# outsidePromini.net
KiCad netlist of a schematic drawn in EAGLE
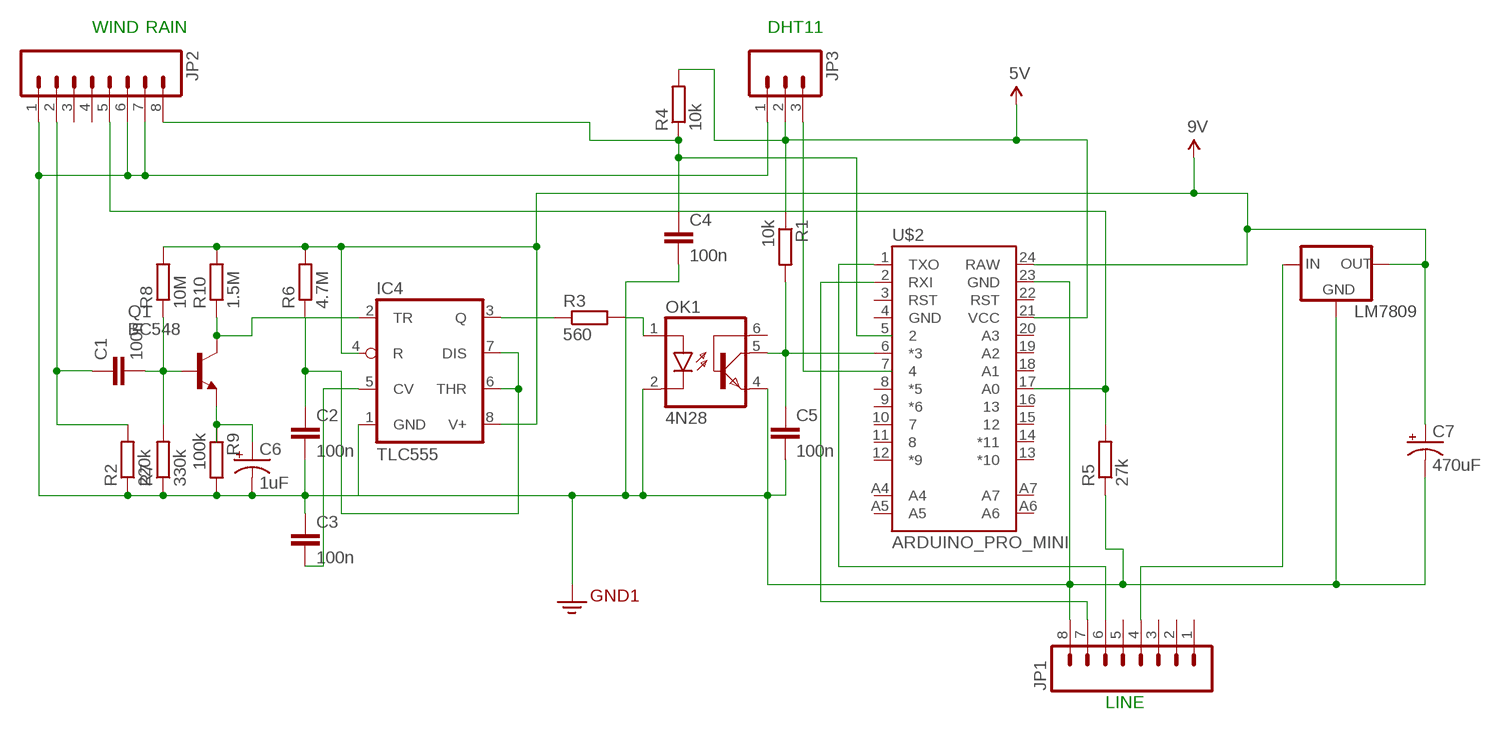
[diagram p0: schematic, sheet 1]

(export (version "E")
  (design (tool "Eeschema 10.0.6"))
  (components
    (comp (ref "C1")
      (value "100n")
      (footprint "eagle-import:CAP-PTH-SMALL-KIT")
      (libsource (lib "eagle-import") (part "0.1UF-50V-20%(PTH)KIT-EZ"))
    )
    (comp (ref "C2")
      (value "100n")
      (footprint "eagle-import:CAP-PTH-SMALL-KIT")
      (libsource (lib "eagle-import") (part "0.1UF-50V-20%(PTH)KIT-EZ"))
    )
    (comp (ref "C3")
      (value "100n")
      (footprint "eagle-import:CAP-PTH-SMALL-KIT")
      (libsource (lib "eagle-import") (part "0.1UF-50V-20%(PTH)KIT-EZ"))
    )
    (comp (ref "C4")
      (value "100n")
      (footprint "eagle-import:CAP-PTH-SMALL-KIT")
      (libsource (lib "eagle-import") (part "0.1UF-50V-20%(PTH)KIT-EZ"))
    )
    (comp (ref "C5")
      (value "100n")
      (footprint "eagle-import:CAP-PTH-SMALL-KIT")
      (libsource (lib "eagle-import") (part "0.1UF-50V-20%(PTH)KIT-EZ"))
    )
    (comp (ref "C6")
      (value "1uF")
      (footprint "eagle-import:CPOL-RADIAL-100UF-25V")
      (libsource (lib "eagle-import") (part "CAP_POLPTH1"))
    )
    (comp (ref "C7")
      (value "470uF")
      (footprint "eagle-import:CPOL-RADIAL-100UF-25V")
      (libsource (lib "eagle-import") (part "CAP_POLPTH1"))
    )
    (comp (ref "IC4")
      (value "TLC555")
      (footprint "eagle-import:DIL08")
      (libsource (lib "eagle-import") (part "555NLM"))
    )
    (comp (ref "JP1")
      (value "M08LOCK_LONGPADS")
      (footprint "eagle-import:1X08_LOCK_LONGPADS")
      (libsource (lib "eagle-import") (part "M08LOCK_LONGPADS"))
    )
    (comp (ref "JP2")
      (value "M08LOCK_LONGPADS")
      (footprint "eagle-import:1X08_LOCK_LONGPADS")
      (libsource (lib "eagle-import") (part "M08LOCK_LONGPADS"))
    )
    (comp (ref "JP3")
      (value "M03LOCK_LONGPADS")
      (footprint "eagle-import:1X03_LOCK_LONGPADS")
      (libsource (lib "eagle-import") (part "M03LOCK_LONGPADS"))
    )
    (comp (ref "LM7809")
      (value "78XXS")
      (footprint "eagle-import:78XXS")
      (libsource (lib "eagle-import") (part "78XXS"))
    )
    (comp (ref "OK1")
      (value "4N28")
      (footprint "eagle-import:DIL06")
      (fields (field (name "MF") "FAIRCHILD SEMICONDUCTOR") (field (name "MPN") "4N37"))
      (libsource (lib "eagle-import") (part "4N37"))
    )
    (comp (ref "Q1")
      (value "BC548")
      (footprint "eagle-import:TO92-EBC")
      (libsource (lib "eagle-import") (part "BC548"))
    )
    (comp (ref "R1")
      (value "10k")
      (footprint "eagle-import:0204_5")
      (libsource (lib "eagle-import") (part "R-EU_0204/5"))
    )
    (comp (ref "R2")
      (value "220k")
      (footprint "eagle-import:0204_5")
      (libsource (lib "eagle-import") (part "R-EU_0204/5"))
    )
    (comp (ref "R3")
      (value "560")
      (footprint "eagle-import:0204_5")
      (libsource (lib "eagle-import") (part "R-EU_0204/5"))
    )
    (comp (ref "R4")
      (value "10k")
      (footprint "eagle-import:0204_5")
      (libsource (lib "eagle-import") (part "R-EU_0204/5"))
    )
    (comp (ref "R5")
      (value "27k")
      (footprint "eagle-import:0204_5")
      (libsource (lib "eagle-import") (part "R-EU_0204/5"))
    )
    (comp (ref "R6")
      (value "4.7M")
      (footprint "eagle-import:0204_5")
      (libsource (lib "eagle-import") (part "R-EU_0204/5"))
    )
    (comp (ref "R7")
      (value "330k")
      (footprint "eagle-import:0204_5")
      (libsource (lib "eagle-import") (part "R-EU_0204/5"))
    )
    (comp (ref "R8")
      (value "10M")
      (footprint "eagle-import:0204_5")
      (libsource (lib "eagle-import") (part "R-EU_0204/5"))
    )
    (comp (ref "R9")
      (value "100k")
      (footprint "eagle-import:0204_5")
      (libsource (lib "eagle-import") (part "R-EU_0204/5"))
    )
    (comp (ref "R10")
      (value "1.5M")
      (footprint "eagle-import:0204_5")
      (libsource (lib "eagle-import") (part "R-EU_0204/5"))
    )
    (comp (ref "U$2")
      (value "ARDUINO_PRO_MINI")
      (footprint "eagle-import:ARDUINO_PRO_MINI")
      (libsource (lib "eagle-import") (part "ARDUINO_PRO_MINI"))
    )
  )
  (nets
    (net (code "1") (name "5V") (class "Default")
      (node (ref "C7") (pin "1") (pinfunction "+_1") (pintype "passive"))
      (node (ref "IC4") (pin "4") (pinfunction "R_4") (pintype "input"))
      (node (ref "IC4") (pin "8") (pinfunction "V+_8") (pintype "power_in"))
      (node (ref "JP3") (pin "2") (pinfunction "2_2") (pintype "passive"))
      (node (ref "LM7809") (pin "OUT") (pinfunction "OUT_OUT") (pintype "passive"))
      (node (ref "R1") (pin "1") (pinfunction "1_1") (pintype "passive"))
      (node (ref "R10") (pin "2") (pinfunction "2_2") (pintype "passive"))
      (node (ref "R4") (pin "2") (pinfunction "2_2") (pintype "passive"))
      (node (ref "R6") (pin "2") (pinfunction "2_2") (pintype "passive"))
      (node (ref "R8") (pin "2") (pinfunction "2_2") (pintype "passive"))
      (node (ref "U$2") (pin "21") (pinfunction "VCC_21") (pintype "bidirectional"))
      (node (ref "U$2") (pin "24") (pinfunction "RAW_24") (pintype "bidirectional"))
    )
    (net (code "2") (name "GND") (class "Default")
      (node (ref "C2") (pin "2") (pinfunction "2_2") (pintype "passive"))
      (node (ref "C3") (pin "1") (pinfunction "1_1") (pintype "passive"))
      (node (ref "C4") (pin "2") (pinfunction "2_2") (pintype "passive"))
      (node (ref "C5") (pin "2") (pinfunction "2_2") (pintype "passive"))
      (node (ref "C6") (pin "2") (pinfunction "-_2") (pintype "passive"))
      (node (ref "C7") (pin "2") (pinfunction "-_2") (pintype "passive"))
      (node (ref "IC4") (pin "1") (pinfunction "GND_1") (pintype "power_in"))
      (node (ref "JP1") (pin "8") (pinfunction "8_8") (pintype "passive"))
      (node (ref "JP2") (pin "1") (pinfunction "1_1") (pintype "passive"))
      (node (ref "JP2") (pin "6") (pinfunction "6_6") (pintype "passive"))
      (node (ref "JP2") (pin "7") (pinfunction "7_7") (pintype "passive"))
      (node (ref "JP3") (pin "1") (pinfunction "1_1") (pintype "passive"))
      (node (ref "LM7809") (pin "GND") (pinfunction "GND_GND") (pintype "input"))
      (node (ref "OK1") (pin "2") (pinfunction "C_2") (pintype "passive"))
      (node (ref "OK1") (pin "4") (pinfunction "EMI_4") (pintype "passive"))
      (node (ref "R2") (pin "1") (pinfunction "1_1") (pintype "passive"))
      (node (ref "R5") (pin "1") (pinfunction "1_1") (pintype "passive"))
      (node (ref "R7") (pin "1") (pinfunction "1_1") (pintype "passive"))
      (node (ref "R9") (pin "2") (pinfunction "2_2") (pintype "passive"))
      (node (ref "U$2") (pin "23") (pinfunction "GND_23") (pintype "bidirectional"))
    )
    (net (code "3") (name "Net-(C1-Pad1)") (class "Default")
      (node (ref "C1") (pin "1") (pinfunction "1_1") (pintype "passive"))
      (node (ref "JP2") (pin "2") (pinfunction "2_2") (pintype "passive"))
      (node (ref "R2") (pin "2") (pinfunction "2_2") (pintype "passive"))
    )
    (net (code "4") (name "Net-(C1-Pad2)") (class "Default")
      (node (ref "C1") (pin "2") (pinfunction "2_2") (pintype "passive"))
      (node (ref "Q1") (pin "B") (pinfunction "B_B") (pintype "passive"))
      (node (ref "R7") (pin "2") (pinfunction "2_2") (pintype "passive"))
      (node (ref "R8") (pin "1") (pinfunction "1_1") (pintype "passive"))
    )
    (net (code "5") (name "Net-(C4-Pad1)") (class "Default")
      (node (ref "C4") (pin "1") (pinfunction "1_1") (pintype "passive"))
      (node (ref "JP2") (pin "8") (pinfunction "8_8") (pintype "passive"))
      (node (ref "R4") (pin "1") (pinfunction "1_1") (pintype "passive"))
    )
    (net (code "6") (name "Net-(C6-+)") (class "Default")
      (node (ref "C6") (pin "1") (pinfunction "+_1") (pintype "passive"))
      (node (ref "Q1") (pin "E") (pinfunction "E_E") (pintype "passive"))
      (node (ref "R9") (pin "1") (pinfunction "1_1") (pintype "passive"))
    )
    (net (code "7") (name "Net-(IC4-CV)") (class "Default")
      (node (ref "C3") (pin "2") (pinfunction "2_2") (pintype "passive"))
      (node (ref "IC4") (pin "5") (pinfunction "CV_5") (pintype "input"))
    )
    (net (code "8") (name "Net-(IC4-DIS)") (class "Default")
      (node (ref "C2") (pin "1") (pinfunction "1_1") (pintype "passive"))
      (node (ref "IC4") (pin "6") (pinfunction "THR_6") (pintype "input"))
      (node (ref "IC4") (pin "7") (pinfunction "DIS_7") (pintype "input"))
      (node (ref "R6") (pin "1") (pinfunction "1_1") (pintype "passive"))
    )
    (net (code "9") (name "Net-(IC4-Q)") (class "Default")
      (node (ref "IC4") (pin "3") (pinfunction "Q_3") (pintype "output"))
      (node (ref "R3") (pin "1") (pinfunction "1_1") (pintype "passive"))
    )
    (net (code "10") (name "Net-(IC4-TR)") (class "Default")
      (node (ref "IC4") (pin "2") (pinfunction "TR_2") (pintype "input"))
      (node (ref "Q1") (pin "C") (pinfunction "C_C") (pintype "passive"))
      (node (ref "R10") (pin "1") (pinfunction "1_1") (pintype "passive"))
    )
    (net (code "11") (name "Net-(JP1-Pad4)") (class "Default")
      (node (ref "JP1") (pin "4") (pinfunction "4_4") (pintype "passive"))
      (node (ref "LM7809") (pin "IN") (pinfunction "IN_IN") (pintype "input"))
    )
    (net (code "12") (name "Net-(OK1-A)") (class "Default")
      (node (ref "OK1") (pin "1") (pinfunction "A_1") (pintype "passive"))
      (node (ref "R3") (pin "2") (pinfunction "2_2") (pintype "passive"))
    )
    (net (code "13") (name "Net-(OK1-COL)") (class "Default")
      (node (ref "C5") (pin "1") (pinfunction "1_1") (pintype "passive"))
      (node (ref "OK1") (pin "5") (pinfunction "COL_5") (pintype "passive"))
      (node (ref "R1") (pin "2") (pinfunction "2_2") (pintype "passive"))
      (node (ref "U$2") (pin "6") (pinfunction "*3_6") (pintype "bidirectional"))
    )
    (net (code "14") (name "Net-(U$2-A0)") (class "Default")
      (node (ref "JP2") (pin "5") (pinfunction "5_5") (pintype "passive"))
      (node (ref "R5") (pin "2") (pinfunction "2_2") (pintype "passive"))
      (node (ref "U$2") (pin "17") (pinfunction "A0_17") (pintype "bidirectional"))
    )
    (net (code "15") (name "Net-(U$2-RXI)") (class "Default")
      (node (ref "JP1") (pin "7") (pinfunction "7_7") (pintype "passive"))
      (node (ref "U$2") (pin "2") (pinfunction "RXI_2") (pintype "bidirectional"))
    )
    (net (code "16") (name "Net-(U$2-TXO)") (class "Default")
      (node (ref "JP1") (pin "6") (pinfunction "6_6") (pintype "passive"))
      (node (ref "U$2") (pin "1") (pinfunction "TXO_1") (pintype "bidirectional"))
    )
    (net (code "17") (name "unconnected-(JP1-Pad1)") (class "Default")
      (node (ref "JP1") (pin "1") (pinfunction "1_1") (pintype "passive"))
    )
    (net (code "18") (name "unconnected-(JP1-Pad2)") (class "Default")
      (node (ref "JP1") (pin "2") (pinfunction "2_2") (pintype "passive"))
    )
    (net (code "19") (name "unconnected-(JP1-Pad3)") (class "Default")
      (node (ref "JP1") (pin "3") (pinfunction "3_3") (pintype "passive"))
    )
    (net (code "20") (name "unconnected-(JP1-Pad5)") (class "Default")
      (node (ref "JP1") (pin "5") (pinfunction "5_5") (pintype "passive"))
    )
    (net (code "21") (name "unconnected-(JP2-Pad3)") (class "Default")
      (node (ref "JP2") (pin "3") (pinfunction "3_3") (pintype "passive"))
    )
    (net (code "22") (name "unconnected-(JP2-Pad4)") (class "Default")
      (node (ref "JP2") (pin "4") (pinfunction "4_4") (pintype "passive"))
    )
    (net (code "23") (name "unconnected-(JP3-Pad3)") (class "Default")
      (node (ref "JP3") (pin "3") (pinfunction "3_3") (pintype "passive"))
    )
    (net (code "24") (name "unconnected-(OK1-BAS-Pad6)") (class "Default")
      (node (ref "OK1") (pin "6") (pinfunction "BAS_6") (pintype "passive"))
    )
    (net (code "25") (name "unconnected-(U$2-*5-Pad8)") (class "Default")
      (node (ref "U$2") (pin "8") (pinfunction "*5_8") (pintype "bidirectional"))
    )
    (net (code "26") (name "unconnected-(U$2-*6-Pad9)") (class "Default")
      (node (ref "U$2") (pin "9") (pinfunction "*6_9") (pintype "bidirectional"))
    )
    (net (code "27") (name "unconnected-(U$2-*9-Pad12)") (class "Default")
      (node (ref "U$2") (pin "12") (pinfunction "*9_12") (pintype "bidirectional"))
    )
    (net (code "28") (name "unconnected-(U$2-*10-Pad13)") (class "Default")
      (node (ref "U$2") (pin "13") (pinfunction "*10_13") (pintype "bidirectional"))
    )
    (net (code "29") (name "unconnected-(U$2-*11-Pad14)") (class "Default")
      (node (ref "U$2") (pin "14") (pinfunction "*11_14") (pintype "bidirectional"))
    )
    (net (code "30") (name "unconnected-(U$2-2-Pad5)") (class "Default")
      (node (ref "U$2") (pin "5") (pinfunction "2_5") (pintype "bidirectional"))
    )
    (net (code "31") (name "unconnected-(U$2-4-Pad7)") (class "Default")
      (node (ref "U$2") (pin "7") (pinfunction "4_7") (pintype "bidirectional"))
    )
    (net (code "32") (name "unconnected-(U$2-7-Pad10)") (class "Default")
      (node (ref "U$2") (pin "10") (pinfunction "7_10") (pintype "bidirectional"))
    )
    (net (code "33") (name "unconnected-(U$2-8-Pad11)") (class "Default")
      (node (ref "U$2") (pin "11") (pinfunction "8_11") (pintype "bidirectional"))
    )
    (net (code "34") (name "unconnected-(U$2-12-Pad15)") (class "Default")
      (node (ref "U$2") (pin "15") (pinfunction "12_15") (pintype "bidirectional"))
    )
    (net (code "35") (name "unconnected-(U$2-13-Pad16)") (class "Default")
      (node (ref "U$2") (pin "16") (pinfunction "13_16") (pintype "bidirectional"))
    )
    (net (code "36") (name "unconnected-(U$2-A1-Pad18)") (class "Default")
      (node (ref "U$2") (pin "18") (pinfunction "A1_18") (pintype "bidirectional"))
    )
    (net (code "37") (name "unconnected-(U$2-A2-Pad19)") (class "Default")
      (node (ref "U$2") (pin "19") (pinfunction "A2_19") (pintype "bidirectional"))
    )
    (net (code "38") (name "unconnected-(U$2-A3-Pad20)") (class "Default")
      (node (ref "U$2") (pin "20") (pinfunction "A3_20") (pintype "bidirectional"))
    )
    (net (code "39") (name "unconnected-(U$2-GND-Pad4)") (class "Default")
      (node (ref "U$2") (pin "4") (pinfunction "GND_4") (pintype "bidirectional"))
    )
    (net (code "40") (name "unconnected-(U$2-PadA4)") (class "Default")
      (node (ref "U$2") (pin "A4") (pinfunction "A4_A4") (pintype "bidirectional"))
    )
    (net (code "41") (name "unconnected-(U$2-PadA5)") (class "Default")
      (node (ref "U$2") (pin "A5") (pinfunction "A5_A5") (pintype "bidirectional"))
    )
    (net (code "42") (name "unconnected-(U$2-PadA6)") (class "Default")
      (node (ref "U$2") (pin "A6") (pinfunction "A6_A6") (pintype "bidirectional"))
    )
    (net (code "43") (name "unconnected-(U$2-PadA7)") (class "Default")
      (node (ref "U$2") (pin "A7") (pinfunction "A7_A7") (pintype "bidirectional"))
    )
    (net (code "44") (name "unconnected-(U$2-RST-Pad3)") (class "Default")
      (node (ref "U$2") (pin "3") (pinfunction "RST_3") (pintype "bidirectional"))
    )
    (net (code "45") (name "unconnected-(U$2-RST-Pad22)") (class "Default")
      (node (ref "U$2") (pin "22") (pinfunction "RST_22") (pintype "bidirectional"))
    )
  )
)
